# lcd.net
KiCad netlist of a schematic drawn in Altium Designer
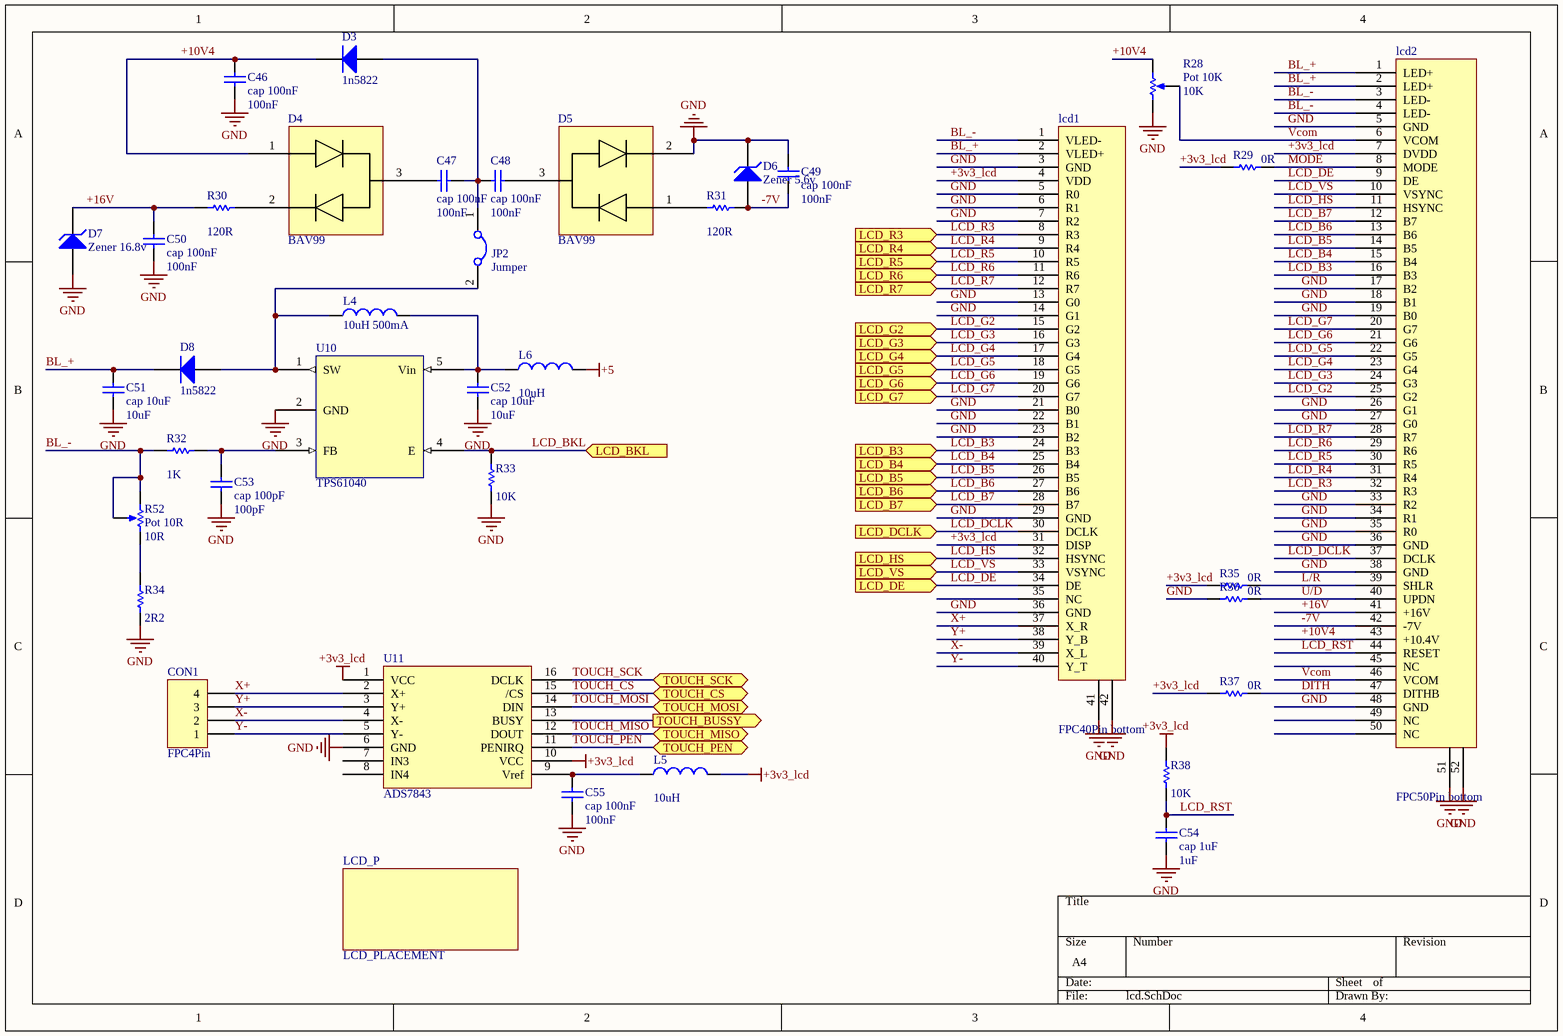
[diagram p0: lcd.SchDoc]

(export (version "E")
  (design (tool "Eeschema 10.0.6"))
  (components
    (comp (ref "C46")
      (value "cap 100nF")
      (footprint "Cap 805")
      (description "Capacitor")
      (fields (field (name "ALTIUM_VALUE") "100nF") (field (name "PUBLISHER") "Altium Limited"))
      (libsource (lib "Miscellaneous Devices") (part "Cap"))
    )
    (comp (ref "C47")
      (value "cap 100nF")
      (footprint "Cap 805")
      (description "Capacitor")
      (fields (field (name "ALTIUM_VALUE") "100nF") (field (name "PUBLISHER") "Altium Limited"))
      (libsource (lib "Miscellaneous Devices") (part "Cap"))
    )
    (comp (ref "C48")
      (value "cap 100nF")
      (footprint "Cap 805")
      (description "Capacitor")
      (fields (field (name "ALTIUM_VALUE") "100nF") (field (name "PUBLISHER") "Altium Limited"))
      (libsource (lib "Miscellaneous Devices") (part "Cap"))
    )
    (comp (ref "C49")
      (value "cap 100nF")
      (footprint "Cap 805")
      (description "Capacitor")
      (fields (field (name "ALTIUM_VALUE") "100nF") (field (name "PUBLISHER") "Altium Limited"))
      (libsource (lib "Miscellaneous Devices") (part "Cap"))
    )
    (comp (ref "C50")
      (value "cap 100nF")
      (footprint "Cap 805")
      (description "Capacitor")
      (fields (field (name "ALTIUM_VALUE") "100nF") (field (name "PUBLISHER") "Altium Limited"))
      (libsource (lib "Miscellaneous Devices") (part "Cap"))
    )
    (comp (ref "C51")
      (value "cap 10uF")
      (footprint "Cap 805")
      (description "Capacitor")
      (fields (field (name "ALTIUM_VALUE") "10uF") (field (name "PUBLISHER") "Altium Limited"))
      (libsource (lib "Miscellaneous Devices") (part "Cap"))
    )
    (comp (ref "C52")
      (value "cap 10uF")
      (footprint "Cap 805")
      (description "Capacitor")
      (fields (field (name "ALTIUM_VALUE") "10uF") (field (name "PUBLISHER") "Altium Limited"))
      (libsource (lib "Miscellaneous Devices") (part "Cap"))
    )
    (comp (ref "C53")
      (value "cap 100pF")
      (footprint "Cap 805")
      (description "Capacitor")
      (fields (field (name "ALTIUM_VALUE") "100pF") (field (name "PUBLISHER") "Altium Limited"))
      (libsource (lib "Miscellaneous Devices") (part "Cap"))
    )
    (comp (ref "C54")
      (value "cap 1uF")
      (footprint "Cap 805")
      (description "Capacitor")
      (fields (field (name "ALTIUM_VALUE") "1uF") (field (name "PUBLISHER") "Altium Limited"))
      (libsource (lib "Miscellaneous Devices") (part "Cap"))
    )
    (comp (ref "C55")
      (value "cap 100nF")
      (footprint "Cap 805")
      (description "Capacitor")
      (fields (field (name "ALTIUM_VALUE") "100nF") (field (name "PUBLISHER") "Altium Limited"))
      (libsource (lib "Miscellaneous Devices") (part "Cap"))
    )
    (comp (ref "CON1")
      (value "FPC4Pin")
      (footprint "FPC-4pin-1mm")
      (description "touchpad FPC")
      (fields (field (name "PUBLISHER") "Altium Limited"))
      (libsource (lib "Miscellaneous Connectors") (part "Header 4"))
    )
    (comp (ref "D3")
      (value "1n5822")
      (footprint "SMA DIODE 2")
      (description "1 Amp schottky Diode")
      (fields (field (name "PUBLISHER") "Altium Limited"))
      (libsource (lib "Miscellaneous Devices") (part "Diode 1N4007"))
    )
    (comp (ref "D4")
      (value "BAV99")
      (footprint "Altium:SOT23_BEC_N")
      (description "Schottky Diode package")
      (libsource (lib "") (part "BAV99_1"))
    )
    (comp (ref "D5")
      (value "BAV99")
      (footprint "Altium:SOT23_BEC_N")
      (description "Schottky Diode package")
      (libsource (lib "Schlib1") (part "BAV99"))
    )
    (comp (ref "D6")
      (value "Zener 5.6v")
      (footprint "Diode 1n4148 SMD")
      (description "Zener Diode")
      (fields (field (name "PUBLISHER") "Altium Limited"))
      (libsource (lib "Miscellaneous Devices") (part "D Zener"))
    )
    (comp (ref "D7")
      (value "Zener 16.8v")
      (footprint "Diode 1n4148 SMD")
      (description "Zener Diode")
      (fields (field (name "PUBLISHER") "Altium Limited"))
      (libsource (lib "Miscellaneous Devices") (part "D Zener"))
    )
    (comp (ref "D8")
      (value "1n5822")
      (footprint "SMA DIODE 2")
      (description "1 Amp schottky Diode")
      (fields (field (name "PUBLISHER") "Altium Limited"))
      (libsource (lib "Miscellaneous Devices") (part "Diode 1N4007"))
    )
    (comp (ref "JP2")
      (value "Jumper")
      (footprint "Jumper Small - 2.54 - GRAY")
      (description "50pin lcd select")
      (libsource (lib "Altium (2)") (part "Jumper"))
    )
    (comp (ref "L4")
      (value "10uH 500mA")
      (footprint "Inductor SMD 3x3.2mm")
      (description "Inductor 3*3.2mm")
      (fields (field (name "Comment") "inductor 10uH 500mA") (field (name "PUBLISHER") "Altium Limited"))
      (libsource (lib "Miscellaneous Devices") (part "Inductor"))
    )
    (comp (ref "L5")
      (value "10uH")
      (footprint "IND1206")
      (description "Inductor")
      (fields (field (name "Comment") "inductor 10uH") (field (name "PUBLISHER") "Altium Limited"))
      (libsource (lib "Miscellaneous Devices") (part "Inductor"))
    )
    (comp (ref "L6")
      (value "10uH")
      (footprint "IND1206")
      (description "Inductor")
      (fields (field (name "Comment") "inductor 10uH") (field (name "PUBLISHER") "Altium Limited"))
      (libsource (lib "Miscellaneous Devices") (part "Inductor"))
    )
    (comp (ref "lcd1")
      (value "FPC40Pin bottom")
      (footprint "FPC40")
      (description "4.3\" RGB LCD")
      (libsource (lib "Schlib1") (part "LCD_40pin"))
    )
    (comp (ref "lcd2")
      (value "FPC50Pin bottom")
      (footprint "FPC50pin")
      (description "7\" LCD")
      (libsource (lib "Schlib1") (part "LCD_50pin"))
    )
    (comp (ref "LCD_P")
      (value "LCD_PLACEMENT")
      (footprint "LCD_7\"_placement")
      (libsource (lib "Schlib1") (part "LCD_PLACEMENT"))
    )
    (comp (ref "R28")
      (value "Pot 10K")
      (footprint "Multi Turn 02")
      (description "Potentiometer")
      (fields (field (name "ALTIUM_VALUE") "10K") (field (name "PUBLISHER") "Altium Limited"))
      (libsource (lib "Miscellaneous Devices") (part "RPot"))
    )
    (comp (ref "R29")
      (value "0R")
      (footprint "RES 0805 (2012X06L)")
      (description "Resistor")
      (fields (field (name "Comment") "Res 0R") (field (name "PUBLISHER") "Altium Limited"))
      (libsource (lib "Miscellaneous Devices") (part "Res1"))
    )
    (comp (ref "R30")
      (value "120R")
      (footprint "RES 0805 (2012X06L)")
      (description "Resistor")
      (fields (field (name "Comment") "Res 120R") (field (name "PUBLISHER") "Altium Limited"))
      (libsource (lib "Miscellaneous Devices") (part "Res1"))
    )
    (comp (ref "R31")
      (value "120R")
      (footprint "RES 0805 (2012X06L)")
      (description "Resistor")
      (fields (field (name "Comment") "Res 120R") (field (name "PUBLISHER") "Altium Limited"))
      (libsource (lib "Miscellaneous Devices") (part "Res1"))
    )
    (comp (ref "R32")
      (value "1K")
      (footprint "RES 0805 (2012X06L)")
      (description "Resistor")
      (fields (field (name "Comment") "Res 1K") (field (name "PUBLISHER") "Altium Limited"))
      (libsource (lib "Miscellaneous Devices") (part "Res1"))
    )
    (comp (ref "R33")
      (value "10K")
      (footprint "RES 0805 (2012X06L)")
      (description "Resistor")
      (fields (field (name "Comment") "Res 10K") (field (name "PUBLISHER") "Altium Limited"))
      (libsource (lib "Miscellaneous Devices") (part "Res1"))
    )
    (comp (ref "R34")
      (value "2R2")
      (footprint "RES 0805 (2012X06L)")
      (description "Resistor")
      (fields (field (name "Comment") "Res 2R2") (field (name "PUBLISHER") "Altium Limited"))
      (libsource (lib "Miscellaneous Devices") (part "Res1"))
    )
    (comp (ref "R35")
      (value "0R")
      (footprint "RES 0805 (2012X06L)")
      (description "Resistor")
      (fields (field (name "Comment") "Res 0R") (field (name "PUBLISHER") "Altium Limited"))
      (libsource (lib "Miscellaneous Devices") (part "Res1"))
    )
    (comp (ref "R36")
      (value "0R")
      (footprint "RES 0805 (2012X06L)")
      (description "Resistor")
      (fields (field (name "Comment") "Res 0R") (field (name "PUBLISHER") "Altium Limited"))
      (libsource (lib "Miscellaneous Devices") (part "Res1"))
    )
    (comp (ref "R37")
      (value "0R")
      (footprint "RES 0805 (2012X06L)")
      (description "Resistor")
      (fields (field (name "Comment") "Res 0R") (field (name "PUBLISHER") "Altium Limited"))
      (libsource (lib "Miscellaneous Devices") (part "Res1"))
    )
    (comp (ref "R38")
      (value "10K")
      (footprint "RES 0805 (2012X06L)")
      (description "Resistor")
      (fields (field (name "Comment") "Res 10K") (field (name "PUBLISHER") "Altium Limited"))
      (libsource (lib "Miscellaneous Devices") (part "Res1"))
    )
    (comp (ref "R52")
      (value "Pot 10R")
      (footprint "Multi Turn 02")
      (description "Potentiometer")
      (fields (field (name "ALTIUM_VALUE") "10R") (field (name "PUBLISHER") "Altium Limited"))
      (libsource (lib "Miscellaneous Devices") (part "RPot"))
    )
    (comp (ref "U10")
      (value "TPS61040")
      (footprint "SOT23-5_N")
      (description "pwm led controller")
      (libsource (lib "ssd1963") (part "TPS61040"))
    )
    (comp (ref "U11")
      (value "ADS7843")
      (footprint "XPT")
      (description "SPI touch")
      (libsource (lib "Schlib1") (part "ADS7843"))
    )
  )
  (nets
    (net (code "1") (name "+3v3_lcd") (class "Default")
      (node (ref "L5") (pin "2") (pinfunction "2_2") (pintype "passive"))
      (node (ref "R29") (pin "2") (pinfunction "2_2") (pintype "passive"))
      (node (ref "R35") (pin "2") (pinfunction "2_2") (pintype "passive"))
      (node (ref "R37") (pin "2") (pinfunction "2_2") (pintype "passive"))
      (node (ref "R38") (pin "2") (pinfunction "2_2") (pintype "passive"))
      (node (ref "U11") (pin "1") (pinfunction "VCC_1") (pintype "passive"))
      (node (ref "U11") (pin "10") (pinfunction "VCC_10") (pintype "passive"))
      (node (ref "lcd1") (pin "31") (pinfunction "DISP_31") (pintype "passive"))
      (node (ref "lcd1") (pin "4") (pinfunction "VDD_4") (pintype "passive"))
      (node (ref "lcd2") (pin "7") (pinfunction "DVDD_7") (pintype "passive"))
    )
    (net (code "2") (name "+5") (class "Default")
      (node (ref "L6") (pin "2") (pinfunction "2_2") (pintype "passive"))
    )
    (net (code "3") (name "/+10V4") (class "Default")
      (node (ref "C46") (pin "1") (pinfunction "1_1") (pintype "passive"))
      (node (ref "D3") (pin "2") (pinfunction "K_2") (pintype "passive"))
      (node (ref "D4") (pin "1") (pinfunction "1_1") (pintype "passive"))
      (node (ref "R28") (pin "2") (pinfunction "BOT_2") (pintype "passive"))
      (node (ref "lcd2") (pin "43") (pinfunction "+10.4V_43") (pintype "passive"))
    )
    (net (code "4") (name "/+16V") (class "Default")
      (node (ref "C50") (pin "1") (pinfunction "1_1") (pintype "passive"))
      (node (ref "D7") (pin "2") (pinfunction "K_2") (pintype "passive"))
      (node (ref "R30") (pin "2") (pinfunction "2_2") (pintype "passive"))
      (node (ref "lcd2") (pin "41") (pinfunction "+16V_41") (pintype "passive"))
    )
    (net (code "5") (name "/-7V") (class "Default")
      (node (ref "C49") (pin "2") (pinfunction "2_2") (pintype "passive"))
      (node (ref "D6") (pin "1") (pinfunction "A_1") (pintype "passive"))
      (node (ref "R31") (pin "1") (pinfunction "1_1") (pintype "passive"))
      (node (ref "lcd2") (pin "42") (pinfunction "-7V_42") (pintype "passive"))
    )
    (net (code "6") (name "/BL_+") (class "Default")
      (node (ref "C51") (pin "1") (pinfunction "1_1") (pintype "passive"))
      (node (ref "D8") (pin "2") (pinfunction "K_2") (pintype "passive"))
      (node (ref "lcd1") (pin "2") (pinfunction "VLED+_2") (pintype "passive"))
      (node (ref "lcd2") (pin "1") (pinfunction "LED+_1") (pintype "passive"))
      (node (ref "lcd2") (pin "2") (pinfunction "LED+_2") (pintype "passive"))
    )
    (net (code "7") (name "/BL_-") (class "Default")
      (node (ref "R32") (pin "2") (pinfunction "2_2") (pintype "passive"))
      (node (ref "R52") (pin "1") (pinfunction "TOP_1") (pintype "passive"))
      (node (ref "R52") (pin "3") (pinfunction "TAP_3") (pintype "passive"))
      (node (ref "lcd1") (pin "1") (pinfunction "VLED-_1") (pintype "passive"))
      (node (ref "lcd2") (pin "3") (pinfunction "LED-_3") (pintype "passive"))
      (node (ref "lcd2") (pin "4") (pinfunction "LED-_4") (pintype "passive"))
    )
    (net (code "8") (name "/DITH") (class "Default")
      (node (ref "R37") (pin "1") (pinfunction "1_1") (pintype "passive"))
      (node (ref "lcd2") (pin "47") (pinfunction "DITHB_47") (pintype "passive"))
    )
    (net (code "9") (name "/LCD_B3") (class "Default")
      (node (ref "lcd1") (pin "24") (pinfunction "B3_24") (pintype "passive"))
      (node (ref "lcd2") (pin "16") (pinfunction "B3_16") (pintype "passive"))
    )
    (net (code "10") (name "/LCD_B4") (class "Default")
      (node (ref "lcd1") (pin "25") (pinfunction "B4_25") (pintype "passive"))
      (node (ref "lcd2") (pin "15") (pinfunction "B4_15") (pintype "passive"))
    )
    (net (code "11") (name "/LCD_B5") (class "Default")
      (node (ref "lcd1") (pin "26") (pinfunction "B5_26") (pintype "passive"))
      (node (ref "lcd2") (pin "14") (pinfunction "B5_14") (pintype "passive"))
    )
    (net (code "12") (name "/LCD_B6") (class "Default")
      (node (ref "lcd1") (pin "27") (pinfunction "B6_27") (pintype "passive"))
      (node (ref "lcd2") (pin "13") (pinfunction "B6_13") (pintype "passive"))
    )
    (net (code "13") (name "/LCD_B7") (class "Default")
      (node (ref "lcd1") (pin "28") (pinfunction "B7_28") (pintype "passive"))
      (node (ref "lcd2") (pin "12") (pinfunction "B7_12") (pintype "passive"))
    )
    (net (code "14") (name "/LCD_BKL") (class "Default")
      (node (ref "R33") (pin "2") (pinfunction "2_2") (pintype "passive"))
      (node (ref "U10") (pin "4") (pinfunction "E_4") (pintype "input"))
    )
    (net (code "15") (name "/LCD_DCLK") (class "Default")
      (node (ref "lcd1") (pin "30") (pinfunction "DCLK_30") (pintype "passive"))
      (node (ref "lcd2") (pin "37") (pinfunction "DCLK_37") (pintype "passive"))
    )
    (net (code "16") (name "/LCD_DE") (class "Default")
      (node (ref "lcd1") (pin "34") (pinfunction "DE_34") (pintype "passive"))
      (node (ref "lcd2") (pin "9") (pinfunction "DE_9") (pintype "passive"))
    )
    (net (code "17") (name "/LCD_G2") (class "Default")
      (node (ref "lcd1") (pin "15") (pinfunction "G2_15") (pintype "passive"))
      (node (ref "lcd2") (pin "25") (pinfunction "G2_25") (pintype "passive"))
    )
    (net (code "18") (name "/LCD_G3") (class "Default")
      (node (ref "lcd1") (pin "16") (pinfunction "G3_16") (pintype "passive"))
      (node (ref "lcd2") (pin "24") (pinfunction "G3_24") (pintype "passive"))
    )
    (net (code "19") (name "/LCD_G4") (class "Default")
      (node (ref "lcd1") (pin "17") (pinfunction "G4_17") (pintype "passive"))
      (node (ref "lcd2") (pin "23") (pinfunction "G4_23") (pintype "passive"))
    )
    (net (code "20") (name "/LCD_G5") (class "Default")
      (node (ref "lcd1") (pin "18") (pinfunction "G5_18") (pintype "passive"))
      (node (ref "lcd2") (pin "22") (pinfunction "G5_22") (pintype "passive"))
    )
    (net (code "21") (name "/LCD_G6") (class "Default")
      (node (ref "lcd1") (pin "19") (pinfunction "G6_19") (pintype "passive"))
      (node (ref "lcd2") (pin "21") (pinfunction "G6_21") (pintype "passive"))
    )
    (net (code "22") (name "/LCD_G7") (class "Default")
      (node (ref "lcd1") (pin "20") (pinfunction "G7_20") (pintype "passive"))
      (node (ref "lcd2") (pin "20") (pinfunction "G7_20") (pintype "passive"))
    )
    (net (code "23") (name "/LCD_HS") (class "Default")
      (node (ref "lcd1") (pin "32") (pinfunction "HSYNC_32") (pintype "passive"))
      (node (ref "lcd2") (pin "11") (pinfunction "HSYNC_11") (pintype "passive"))
    )
    (net (code "24") (name "/LCD_R3") (class "Default")
      (node (ref "lcd1") (pin "8") (pinfunction "R3_8") (pintype "passive"))
      (node (ref "lcd2") (pin "32") (pinfunction "R3_32") (pintype "passive"))
    )
    (net (code "25") (name "/LCD_R4") (class "Default")
      (node (ref "lcd1") (pin "9") (pinfunction "R4_9") (pintype "passive"))
      (node (ref "lcd2") (pin "31") (pinfunction "R4_31") (pintype "passive"))
    )
    (net (code "26") (name "/LCD_R5") (class "Default")
      (node (ref "lcd1") (pin "10") (pinfunction "R5_10") (pintype "passive"))
      (node (ref "lcd2") (pin "30") (pinfunction "R5_30") (pintype "passive"))
    )
    (net (code "27") (name "/LCD_R6") (class "Default")
      (node (ref "lcd1") (pin "11") (pinfunction "R6_11") (pintype "passive"))
      (node (ref "lcd2") (pin "29") (pinfunction "R6_29") (pintype "passive"))
    )
    (net (code "28") (name "/LCD_R7") (class "Default")
      (node (ref "lcd1") (pin "12") (pinfunction "R7_12") (pintype "passive"))
      (node (ref "lcd2") (pin "28") (pinfunction "R7_28") (pintype "passive"))
    )
    (net (code "29") (name "/LCD_RST") (class "Default")
      (node (ref "C54") (pin "2") (pinfunction "2_2") (pintype "passive"))
      (node (ref "R38") (pin "1") (pinfunction "1_1") (pintype "passive"))
      (node (ref "lcd2") (pin "44") (pinfunction "RESET_44") (pintype "passive"))
    )
    (net (code "30") (name "/LCD_VS") (class "Default")
      (node (ref "lcd1") (pin "33") (pinfunction "VSYNC_33") (pintype "passive"))
      (node (ref "lcd2") (pin "10") (pinfunction "VSYNC_10") (pintype "passive"))
    )
    (net (code "31") (name "/L{slash}R") (class "Default")
      (node (ref "R35") (pin "1") (pinfunction "1_1") (pintype "passive"))
      (node (ref "lcd2") (pin "39") (pinfunction "SHLR_39") (pintype "passive"))
    )
    (net (code "32") (name "/MODE") (class "Default")
      (node (ref "R29") (pin "1") (pinfunction "1_1") (pintype "passive"))
      (node (ref "lcd2") (pin "8") (pinfunction "MODE_8") (pintype "passive"))
    )
    (net (code "33") (name "/TOUCH_BUSSY") (class "Default")
      (node (ref "U11") (pin "13") (pinfunction "BUSY_13") (pintype "passive"))
    )
    (net (code "34") (name "/TOUCH_CS") (class "Default")
      (node (ref "U11") (pin "15") (pinfunction "/CS_15") (pintype "passive"))
    )
    (net (code "35") (name "/TOUCH_MISO") (class "Default")
      (node (ref "U11") (pin "12") (pinfunction "DOUT_12") (pintype "passive"))
    )
    (net (code "36") (name "/TOUCH_MOSI") (class "Default")
      (node (ref "U11") (pin "14") (pinfunction "DIN_14") (pintype "passive"))
    )
    (net (code "37") (name "/TOUCH_PEN") (class "Default")
      (node (ref "U11") (pin "11") (pinfunction "PENIRQ_11") (pintype "passive"))
    )
    (net (code "38") (name "/TOUCH_SCK") (class "Default")
      (node (ref "U11") (pin "16") (pinfunction "DCLK_16") (pintype "passive"))
    )
    (net (code "39") (name "/U{slash}D") (class "Default")
      (node (ref "R36") (pin "1") (pinfunction "1_1") (pintype "passive"))
      (node (ref "lcd2") (pin "40") (pinfunction "UPDN_40") (pintype "passive"))
    )
    (net (code "40") (name "/Vcom") (class "Default")
      (node (ref "R28") (pin "3") (pinfunction "TAP_3") (pintype "passive"))
      (node (ref "lcd2") (pin "46") (pinfunction "VCOM_46") (pintype "passive"))
      (node (ref "lcd2") (pin "6") (pinfunction "VCOM_6") (pintype "passive"))
    )
    (net (code "41") (name "/X+") (class "Default")
      (node (ref "CON1") (pin "4") (pinfunction "4_4") (pintype "passive"))
      (node (ref "U11") (pin "2") (pinfunction "X+_2") (pintype "passive"))
      (node (ref "lcd1") (pin "37") (pinfunction "X_R_37") (pintype "passive"))
    )
    (net (code "42") (name "/X-") (class "Default")
      (node (ref "CON1") (pin "2") (pinfunction "2_2") (pintype "passive"))
      (node (ref "U11") (pin "4") (pinfunction "X-_4") (pintype "passive"))
      (node (ref "lcd1") (pin "39") (pinfunction "X_L_39") (pintype "passive"))
    )
    (net (code "43") (name "/Y+") (class "Default")
      (node (ref "CON1") (pin "3") (pinfunction "3_3") (pintype "passive"))
      (node (ref "U11") (pin "3") (pinfunction "Y+_3") (pintype "passive"))
      (node (ref "lcd1") (pin "38") (pinfunction "Y_B_38") (pintype "passive"))
    )
    (net (code "44") (name "/Y-") (class "Default")
      (node (ref "CON1") (pin "1") (pinfunction "1_1") (pintype "passive"))
      (node (ref "U11") (pin "5") (pinfunction "Y-_5") (pintype "passive"))
      (node (ref "lcd1") (pin "40") (pinfunction "Y_T_40") (pintype "passive"))
    )
    (net (code "45") (name "GND") (class "Default")
      (node (ref "C46") (pin "2") (pinfunction "2_2") (pintype "passive"))
      (node (ref "C49") (pin "1") (pinfunction "1_1") (pintype "passive"))
      (node (ref "C50") (pin "2") (pinfunction "2_2") (pintype "passive"))
      (node (ref "C51") (pin "2") (pinfunction "2_2") (pintype "passive"))
      (node (ref "C52") (pin "2") (pinfunction "2_2") (pintype "passive"))
      (node (ref "C53") (pin "2") (pinfunction "2_2") (pintype "passive"))
      (node (ref "C54") (pin "1") (pinfunction "1_1") (pintype "passive"))
      (node (ref "C55") (pin "2") (pinfunction "2_2") (pintype "passive"))
      (node (ref "D5") (pin "2") (pinfunction "2_2") (pintype "passive"))
      (node (ref "D6") (pin "2") (pinfunction "K_2") (pintype "passive"))
      (node (ref "D7") (pin "1") (pinfunction "A_1") (pintype "passive"))
      (node (ref "R28") (pin "1") (pinfunction "TOP_1") (pintype "passive"))
      (node (ref "R33") (pin "1") (pinfunction "1_1") (pintype "passive"))
      (node (ref "R34") (pin "1") (pinfunction "1_1") (pintype "passive"))
      (node (ref "R36") (pin "2") (pinfunction "2_2") (pintype "passive"))
      (node (ref "U10") (pin "2") (pinfunction "GND_2") (pintype "power_in"))
      (node (ref "U11") (pin "6") (pinfunction "GND_6") (pintype "passive"))
      (node (ref "lcd1") (pin "13") (pinfunction "G0_13") (pintype "passive"))
      (node (ref "lcd1") (pin "14") (pinfunction "G1_14") (pintype "passive"))
      (node (ref "lcd1") (pin "21") (pinfunction "B0_21") (pintype "passive"))
      (node (ref "lcd1") (pin "22") (pinfunction "B1_22") (pintype "passive"))
      (node (ref "lcd1") (pin "23") (pinfunction "B2_23") (pintype "passive"))
      (node (ref "lcd1") (pin "29") (pinfunction "GND_29") (pintype "passive"))
      (node (ref "lcd1") (pin "3") (pinfunction "GND_3") (pintype "passive"))
      (node (ref "lcd1") (pin "36") (pinfunction "GND_36") (pintype "passive"))
      (node (ref "lcd1") (pin "41") (pinfunction "41_41") (pintype "passive"))
      (node (ref "lcd1") (pin "42") (pinfunction "42_42") (pintype "passive"))
      (node (ref "lcd1") (pin "5") (pinfunction "R0_5") (pintype "passive"))
      (node (ref "lcd1") (pin "6") (pinfunction "R1_6") (pintype "passive"))
      (node (ref "lcd1") (pin "7") (pinfunction "R2_7") (pintype "passive"))
      (node (ref "lcd2") (pin "17") (pinfunction "B2_17") (pintype "passive"))
      (node (ref "lcd2") (pin "18") (pinfunction "B1_18") (pintype "passive"))
      (node (ref "lcd2") (pin "19") (pinfunction "B0_19") (pintype "passive"))
      (node (ref "lcd2") (pin "26") (pinfunction "G1_26") (pintype "passive"))
      (node (ref "lcd2") (pin "27") (pinfunction "G0_27") (pintype "passive"))
      (node (ref "lcd2") (pin "33") (pinfunction "R2_33") (pintype "passive"))
      (node (ref "lcd2") (pin "34") (pinfunction "R1_34") (pintype "passive"))
      (node (ref "lcd2") (pin "35") (pinfunction "R0_35") (pintype "passive"))
      (node (ref "lcd2") (pin "36") (pinfunction "GND_36") (pintype "passive"))
      (node (ref "lcd2") (pin "38") (pinfunction "GND_38") (pintype "passive"))
      (node (ref "lcd2") (pin "48") (pinfunction "GND_48") (pintype "passive"))
      (node (ref "lcd2") (pin "5") (pinfunction "GND_5") (pintype "passive"))
      (node (ref "lcd2") (pin "51") (pinfunction "51_51") (pintype "passive"))
      (node (ref "lcd2") (pin "52") (pinfunction "52_52") (pintype "passive"))
    )
    (net (code "46") (name "Net-(C47-Pad2)") (class "Default")
      (node (ref "C47") (pin "2") (pinfunction "2_2") (pintype "passive"))
      (node (ref "D4") (pin "3") (pinfunction "3_3") (pintype "passive"))
    )
    (net (code "47") (name "Net-(C48-Pad1)") (class "Default")
      (node (ref "C48") (pin "1") (pinfunction "1_1") (pintype "passive"))
      (node (ref "D5") (pin "3") (pinfunction "3_3") (pintype "passive"))
    )
    (net (code "48") (name "Net-(D3-A)") (class "Default")
      (node (ref "C47") (pin "1") (pinfunction "1_1") (pintype "passive"))
      (node (ref "C48") (pin "2") (pinfunction "2_2") (pintype "passive"))
      (node (ref "D3") (pin "1") (pinfunction "A_1") (pintype "passive"))
      (node (ref "JP2") (pin "1") (pinfunction "1_1") (pintype "passive"))
    )
    (net (code "49") (name "Net-(D4-Pad2)") (class "Default")
      (node (ref "D4") (pin "2") (pinfunction "2_2") (pintype "passive"))
      (node (ref "R30") (pin "1") (pinfunction "1_1") (pintype "passive"))
    )
    (net (code "50") (name "Net-(D5-Pad1)") (class "Default")
      (node (ref "D5") (pin "1") (pinfunction "1_1") (pintype "passive"))
      (node (ref "R31") (pin "2") (pinfunction "2_2") (pintype "passive"))
    )
    (net (code "51") (name "Net-(D8-A)") (class "Default")
      (node (ref "D8") (pin "1") (pinfunction "A_1") (pintype "passive"))
      (node (ref "JP2") (pin "2") (pinfunction "2_2") (pintype "passive"))
      (node (ref "L4") (pin "1") (pinfunction "1_1") (pintype "passive"))
      (node (ref "U10") (pin "1") (pinfunction "SW_1") (pintype "output"))
    )
    (net (code "52") (name "Net-(R52-BOT)") (class "Default")
      (node (ref "R34") (pin "2") (pinfunction "2_2") (pintype "passive"))
      (node (ref "R52") (pin "2") (pinfunction "BOT_2") (pintype "passive"))
    )
    (net (code "53") (name "Net-(U10-FB)") (class "Default")
      (node (ref "C53") (pin "1") (pinfunction "1_1") (pintype "passive"))
      (node (ref "R32") (pin "1") (pinfunction "1_1") (pintype "passive"))
      (node (ref "U10") (pin "3") (pinfunction "FB_3") (pintype "input"))
    )
    (net (code "54") (name "Net-(U10-Vin)") (class "Default")
      (node (ref "C52") (pin "1") (pinfunction "1_1") (pintype "passive"))
      (node (ref "L4") (pin "2") (pinfunction "2_2") (pintype "passive"))
      (node (ref "L6") (pin "1") (pinfunction "1_1") (pintype "passive"))
      (node (ref "U10") (pin "5") (pinfunction "Vin_5") (pintype "input"))
    )
    (net (code "55") (name "Net-(U11-Vref)") (class "Default")
      (node (ref "C55") (pin "1") (pinfunction "1_1") (pintype "passive"))
      (node (ref "L5") (pin "1") (pinfunction "1_1") (pintype "passive"))
      (node (ref "U11") (pin "9") (pinfunction "Vref_9") (pintype "passive"))
    )
    (net (code "56") (name "unconnected-(U11-IN3-Pad7)") (class "Default")
      (node (ref "U11") (pin "7") (pinfunction "IN3_7") (pintype "passive"))
    )
    (net (code "57") (name "unconnected-(U11-IN4-Pad8)") (class "Default")
      (node (ref "U11") (pin "8") (pinfunction "IN4_8") (pintype "passive"))
    )
    (net (code "58") (name "unconnected-(lcd1-NC-Pad35)") (class "Default")
      (node (ref "lcd1") (pin "35") (pinfunction "NC_35") (pintype "passive"))
    )
    (net (code "59") (name "unconnected-(lcd2-NC-Pad45)") (class "Default")
      (node (ref "lcd2") (pin "45") (pinfunction "NC_45") (pintype "passive"))
    )
    (net (code "60") (name "unconnected-(lcd2-NC-Pad49)") (class "Default")
      (node (ref "lcd2") (pin "49") (pinfunction "NC_49") (pintype "passive"))
    )
    (net (code "61") (name "unconnected-(lcd2-NC-Pad50)") (class "Default")
      (node (ref "lcd2") (pin "50") (pinfunction "NC_50") (pintype "passive"))
    )
  )
)
